# am-crystal-rx-lm324.net
KiCad netlist of a schematic drawn in EAGLE
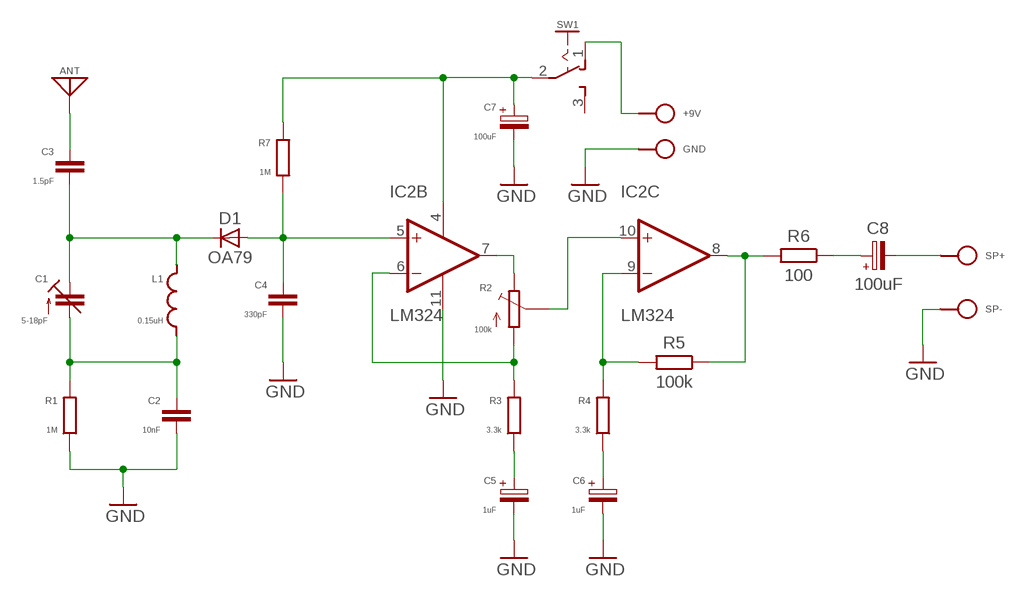
[diagram p0: schematic, sheet 1]

(export (version "E")
  (design (tool "Eeschema 10.0.6"))
  (components
    (comp (ref "+9V")
      (value "BAT+")
      (footprint "eagle-import:SPAD")
      (libsource (lib "eagle-import") (part "SPAD"))
    )
    (comp (ref "ANT")
      (value "ANT")
      (footprint "eagle-import:SPAD")
      (libsource (lib "eagle-import") (part "ANT"))
    )
    (comp (ref "C1")
      (value "5-18pF")
      (footprint "eagle-import:TRIM-2222-808")
      (libsource (lib "eagle-import") (part "C-TR-PH201272222-808-2PIN"))
    )
    (comp (ref "C2")
      (value "10nF")
      (footprint "eagle-import:C050-025X075_V")
      (libsource (lib "eagle-import") (part "C050-025X075/V"))
    )
    (comp (ref "C3")
      (value "1.5pF")
      (footprint "eagle-import:C050-020X036")
      (libsource (lib "eagle-import") (part "C050-020X036"))
    )
    (comp (ref "C4")
      (value "330pF")
      (footprint "eagle-import:C050-024X044_V")
      (libsource (lib "eagle-import") (part "C050-024X044/V"))
    )
    (comp (ref "C5")
      (value "1uF")
      (footprint "eagle-import:E2.5-4_V")
      (libsource (lib "eagle-import") (part "CPOLE2,5-4/V"))
    )
    (comp (ref "C6")
      (value "1uF")
      (footprint "eagle-import:E2,5-3")
      (libsource (lib "eagle-import") (part "CPOLE2,5-3"))
    )
    (comp (ref "C7")
      (value "100uF")
      (footprint "eagle-import:E5-5_V")
      (libsource (lib "eagle-import") (part "CPOLE5-5/V"))
    )
    (comp (ref "C8")
      (value "100uF")
      (footprint "eagle-import:E2,5-5_V")
      (libsource (lib "eagle-import") (part "CPOLE2,5-5/V"))
    )
    (comp (ref "D1")
      (value "OA79")
      (footprint "eagle-import:OA79-18_V")
      (libsource (lib "eagle-import") (part "OA7918/V"))
    )
    (comp (ref "GND")
      (value "BAT-")
      (footprint "eagle-import:SPAD")
      (libsource (lib "eagle-import") (part "SPAD"))
    )
    (comp (ref "IC2")
      (value "LM324")
      (footprint "eagle-import:DIL14")
      (libsource (lib "eagle-import") (part "LM324N"))
    )
    (comp (ref "L1")
      (value "0.15uH")
      (footprint "eagle-import:L-04-5_5")
      (libsource (lib "eagle-import") (part "L-SHORT04-5/5"))
    )
    (comp (ref "R1")
      (value "1M")
      (footprint "eagle-import:0202_7-V")
      (libsource (lib "eagle-import") (part "R0202/7-V"))
    )
    (comp (ref "R2")
      (value "100k")
      (footprint "eagle-import:B64Y")
      (libsource (lib "eagle-import") (part "TRIM"))
    )
    (comp (ref "R3")
      (value "3.3k")
      (footprint "eagle-import:0202_7")
      (libsource (lib "eagle-import") (part "R0202/7"))
    )
    (comp (ref "R4")
      (value "3.3k")
      (footprint "eagle-import:0202_7-V")
      (libsource (lib "eagle-import") (part "R0202/7-V"))
    )
    (comp (ref "R5")
      (value "100k")
      (footprint "eagle-import:0202_7-V")
      (libsource (lib "eagle-import") (part "R0202/7-V"))
    )
    (comp (ref "R6")
      (value "100")
      (footprint "eagle-import:0202_7-V")
      (libsource (lib "eagle-import") (part "R0202/7-V"))
    )
    (comp (ref "R7")
      (value "1M")
      (footprint "eagle-import:0202_7-V")
      (libsource (lib "eagle-import") (part "R0202/7-V"))
    )
    (comp (ref "SP+")
      (value "SPKR+")
      (footprint "eagle-import:SPAD")
      (libsource (lib "eagle-import") (part "SPAD"))
    )
    (comp (ref "SP-")
      (value "SPKR-")
      (footprint "eagle-import:SPAD")
      (libsource (lib "eagle-import") (part "SPAD"))
    )
    (comp (ref "SW1")
      (value "SL-SW-1P-2T-H")
      (footprint "eagle-import:SLSW-1P2T-H")
      (libsource (lib "eagle-import") (part "SL-SW-1P-2T-H"))
    )
  )
  (nets
    (net (code "1") (name "GND") (class "Default")
      (node (ref "C2") (pin "2") (pinfunction "2_2") (pintype "passive"))
      (node (ref "C4") (pin "2") (pinfunction "2_2") (pintype "passive"))
      (node (ref "C5") (pin "-") (pinfunction "-_-") (pintype "passive"))
      (node (ref "C6") (pin "-") (pinfunction "-_-") (pintype "passive"))
      (node (ref "C7") (pin "-") (pinfunction "-_-") (pintype "passive"))
      (node (ref "GND") (pin "1") (pinfunction "P$1_1") (pintype "bidirectional"))
      (node (ref "IC2") (pin "11") (pinfunction "V-_11") (pintype "power_in"))
      (node (ref "R1") (pin "1") (pinfunction "1_1") (pintype "passive"))
      (node (ref "SP-") (pin "1") (pinfunction "P$1_1") (pintype "bidirectional"))
    )
    (net (code "2") (name "Net-(+9V-P$1)") (class "Default")
      (node (ref "+9V") (pin "1") (pinfunction "P$1_1") (pintype "bidirectional"))
      (node (ref "SW1") (pin "1") (pinfunction "O_1") (pintype "passive"))
    )
    (net (code "3") (name "Net-(ANT-Pad1)") (class "Default")
      (node (ref "ANT") (pin "1") (pinfunction "1_1") (pintype "output"))
      (node (ref "C3") (pin "1") (pinfunction "1_1") (pintype "passive"))
    )
    (net (code "4") (name "Net-(C1-A)") (class "Default")
      (node (ref "C1") (pin "1") (pinfunction "A_1") (pintype "passive"))
      (node (ref "C2") (pin "1") (pinfunction "1_1") (pintype "passive"))
      (node (ref "L1") (pin "1") (pinfunction "1_1") (pintype "passive"))
      (node (ref "R1") (pin "2") (pinfunction "2_2") (pintype "passive"))
    )
    (net (code "5") (name "Net-(C1-E)") (class "Default")
      (node (ref "C1") (pin "2") (pinfunction "E_2") (pintype "passive"))
      (node (ref "C3") (pin "2") (pinfunction "2_2") (pintype "passive"))
      (node (ref "D1") (pin "C") (pinfunction "C_C") (pintype "passive"))
      (node (ref "L1") (pin "2") (pinfunction "2_2") (pintype "passive"))
    )
    (net (code "6") (name "Net-(C5-Pad+)") (class "Default")
      (node (ref "C5") (pin "+") (pinfunction "+_+") (pintype "passive"))
      (node (ref "R3") (pin "1") (pinfunction "1_1") (pintype "passive"))
    )
    (net (code "7") (name "Net-(C6-Pad+)") (class "Default")
      (node (ref "C6") (pin "+") (pinfunction "+_+") (pintype "passive"))
      (node (ref "R4") (pin "1") (pinfunction "1_1") (pintype "passive"))
    )
    (net (code "8") (name "Net-(C8-Pad+)") (class "Default")
      (node (ref "C8") (pin "+") (pinfunction "+_+") (pintype "passive"))
      (node (ref "R6") (pin "1") (pinfunction "1_1") (pintype "passive"))
    )
    (net (code "9") (name "Net-(IC2B-+IN)") (class "Default")
      (node (ref "C4") (pin "1") (pinfunction "1_1") (pintype "passive"))
      (node (ref "D1") (pin "A") (pinfunction "A_A") (pintype "passive"))
      (node (ref "IC2") (pin "5") (pinfunction "+IN_5") (pintype "input"))
      (node (ref "R7") (pin "1") (pinfunction "1_1") (pintype "passive"))
    )
    (net (code "10") (name "Net-(IC2B--IN)") (class "Default")
      (node (ref "IC2") (pin "6") (pinfunction "-IN_6") (pintype "input"))
      (node (ref "R2") (pin "A") (pinfunction "A_A") (pintype "passive"))
      (node (ref "R3") (pin "2") (pinfunction "2_2") (pintype "passive"))
    )
    (net (code "11") (name "Net-(IC2B-OUT)") (class "Default")
      (node (ref "IC2") (pin "7") (pinfunction "OUT_7") (pintype "output"))
      (node (ref "R2") (pin "E") (pinfunction "E_E") (pintype "passive"))
    )
    (net (code "12") (name "Net-(IC2C-+IN)") (class "Default")
      (node (ref "IC2") (pin "10") (pinfunction "+IN_10") (pintype "input"))
      (node (ref "R2") (pin "S") (pinfunction "S_S") (pintype "passive"))
    )
    (net (code "13") (name "Net-(IC2C--IN)") (class "Default")
      (node (ref "IC2") (pin "9") (pinfunction "-IN_9") (pintype "input"))
      (node (ref "R4") (pin "2") (pinfunction "2_2") (pintype "passive"))
      (node (ref "R5") (pin "2") (pinfunction "2_2") (pintype "passive"))
    )
    (net (code "14") (name "Net-(IC2C-OUT)") (class "Default")
      (node (ref "IC2") (pin "8") (pinfunction "OUT_8") (pintype "output"))
      (node (ref "R5") (pin "1") (pinfunction "1_1") (pintype "passive"))
      (node (ref "R6") (pin "2") (pinfunction "2_2") (pintype "passive"))
    )
    (net (code "15") (name "Net-(IC2E-V+)") (class "Default")
      (node (ref "C7") (pin "+") (pinfunction "+_+") (pintype "passive"))
      (node (ref "IC2") (pin "4") (pinfunction "V+_4") (pintype "power_in"))
      (node (ref "R7") (pin "2") (pinfunction "2_2") (pintype "passive"))
      (node (ref "SW1") (pin "2") (pinfunction "P_2") (pintype "passive"))
    )
    (net (code "16") (name "Net-(SP+-P$1)") (class "Default")
      (node (ref "C8") (pin "-") (pinfunction "-_-") (pintype "passive"))
      (node (ref "SP+") (pin "1") (pinfunction "P$1_1") (pintype "bidirectional"))
    )
    (net (code "17") (name "unconnected-(SW1-S-Pad3)") (class "Default")
      (node (ref "SW1") (pin "3") (pinfunction "S_3") (pintype "passive"))
    )
  )
)
